# LoraSPI.net
KiCad netlist of a schematic drawn in Altium Designer
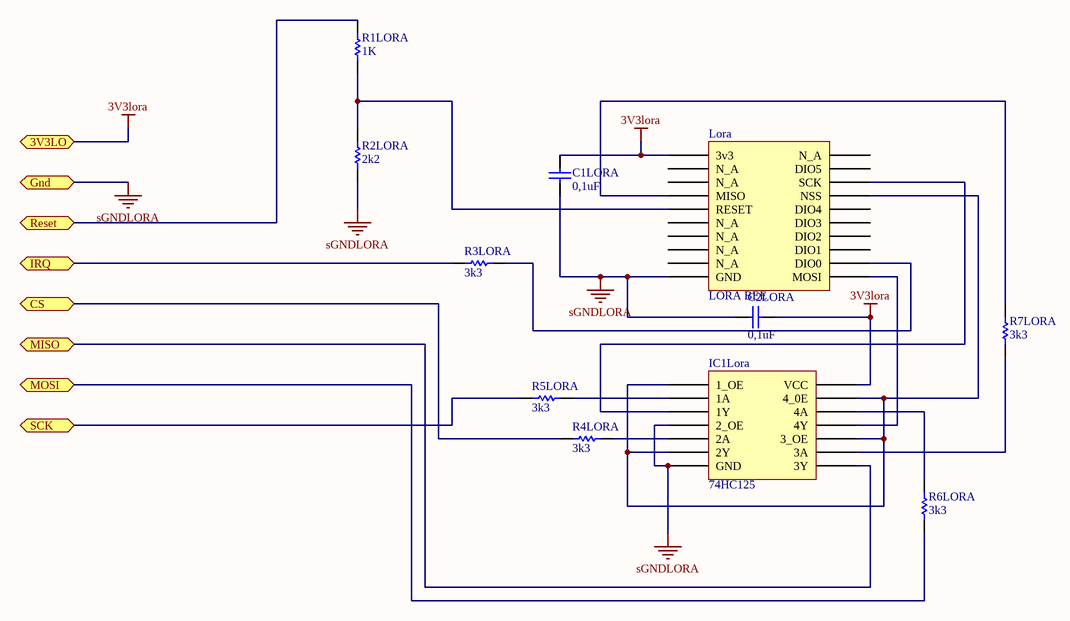
[diagram p0: LoraSPI.SchDoc]

(export (version "E")
  (design (tool "Eeschema 10.0.6"))
  (components
    (comp (ref "C1LORA")
      (value "0,1uF")
      (footprint "CAP100")
      (description "Capacitor")
      (libsource (lib "IDTILab") (part "CAP"))
    )
    (comp (ref "C2LORA")
      (value "0,1uF")
      (footprint "CAP100")
      (description "Capacitor")
      (libsource (lib "IDTILab") (part "CAP"))
    )
    (comp (ref "IC1Lora") (value "74HC125") (footprint "DIP14B") (libsource (lib "IDTILab") (part "74HC125")))
    (comp (ref "Lora") (value "LORA BEE") (footprint "LORABEE") (libsource (lib "IDTILab") (part "LORA BEE")))
    (comp (ref "R1LORA")
      (value "1K")
      (footprint "RES300")
      (description "Resistencia")
      (libsource (lib "IDTILab") (part "RES"))
    )
    (comp (ref "R2LORA")
      (value "2k2")
      (footprint "RES300")
      (description "Resistencia")
      (libsource (lib "IDTILab") (part "RES"))
    )
    (comp (ref "R3LORA")
      (value "3k3")
      (footprint "RES300")
      (description "Resistencia")
      (libsource (lib "IDTILab") (part "RES"))
    )
    (comp (ref "R4LORA")
      (value "3k3")
      (footprint "RES300")
      (description "Resistencia")
      (libsource (lib "IDTILab") (part "RES"))
    )
    (comp (ref "R5LORA")
      (value "3k3")
      (footprint "RES300")
      (description "Resistencia")
      (libsource (lib "IDTILab") (part "RES"))
    )
    (comp (ref "R6LORA")
      (value "3k3")
      (footprint "RES300")
      (description "Resistencia")
      (libsource (lib "IDTILab") (part "RES"))
    )
    (comp (ref "R7LORA")
      (value "3k3")
      (footprint "RES300")
      (description "Resistencia")
      (libsource (lib "IDTILab") (part "RES"))
    )
  )
  (nets
    (net (code "1") (name "/CS") (class "Default")
      (node (ref "R4LORA") (pin "2") (pinfunction "2_2") (pintype "passive"))
    )
    (net (code "2") (name "/IRQ") (class "Default")
      (node (ref "R3LORA") (pin "2") (pinfunction "2_2") (pintype "passive"))
    )
    (net (code "3") (name "/MISO") (class "Default")
      (node (ref "IC1Lora") (pin "8") (pinfunction "3Y_8") (pintype "passive"))
    )
    (net (code "4") (name "/MOSI") (class "Default")
      (node (ref "R6LORA") (pin "1") (pinfunction "1_1") (pintype "passive"))
    )
    (net (code "5") (name "/Reset") (class "Default")
      (node (ref "R1LORA") (pin "2") (pinfunction "2_2") (pintype "passive"))
    )
    (net (code "6") (name "/SCK") (class "Default")
      (node (ref "R5LORA") (pin "2") (pinfunction "2_2") (pintype "passive"))
    )
    (net (code "7") (name "3V3lora") (class "Default")
      (node (ref "C1LORA") (pin "2") (pinfunction "2_2") (pintype "passive"))
      (node (ref "C2LORA") (pin "2") (pinfunction "2_2") (pintype "passive"))
      (node (ref "IC1Lora") (pin "14") (pinfunction "VCC_14") (pintype "passive"))
      (node (ref "Lora") (pin "1") (pinfunction "3v3_1") (pintype "passive"))
    )
    (net (code "8") (name "Net-(IC1Lora-1A)") (class "Default")
      (node (ref "IC1Lora") (pin "2") (pinfunction "1A_2") (pintype "passive"))
      (node (ref "R5LORA") (pin "1") (pinfunction "1_1") (pintype "passive"))
    )
    (net (code "9") (name "Net-(IC1Lora-1Y)") (class "Default")
      (node (ref "IC1Lora") (pin "3") (pinfunction "1Y_3") (pintype "passive"))
      (node (ref "Lora") (pin "18") (pinfunction "SCK_18") (pintype "passive"))
    )
    (net (code "10") (name "Net-(IC1Lora-1_OE)") (class "Default")
      (node (ref "IC1Lora") (pin "1") (pinfunction "1_OE_1") (pintype "passive"))
      (node (ref "IC1Lora") (pin "10") (pinfunction "3_OE_10") (pintype "passive"))
      (node (ref "IC1Lora") (pin "13") (pinfunction "4_0E_13") (pintype "passive"))
      (node (ref "IC1Lora") (pin "6") (pinfunction "2Y_6") (pintype "passive"))
      (node (ref "Lora") (pin "17") (pinfunction "NSS_17") (pintype "passive"))
    )
    (net (code "11") (name "Net-(IC1Lora-2A)") (class "Default")
      (node (ref "IC1Lora") (pin "5") (pinfunction "2A_5") (pintype "passive"))
      (node (ref "R4LORA") (pin "1") (pinfunction "1_1") (pintype "passive"))
    )
    (net (code "12") (name "Net-(IC1Lora-3A)") (class "Default")
      (node (ref "IC1Lora") (pin "9") (pinfunction "3A_9") (pintype "passive"))
      (node (ref "R7LORA") (pin "1") (pinfunction "1_1") (pintype "passive"))
    )
    (net (code "13") (name "Net-(IC1Lora-4A)") (class "Default")
      (node (ref "IC1Lora") (pin "12") (pinfunction "4A_12") (pintype "passive"))
      (node (ref "R6LORA") (pin "2") (pinfunction "2_2") (pintype "passive"))
    )
    (net (code "14") (name "Net-(IC1Lora-4Y)") (class "Default")
      (node (ref "IC1Lora") (pin "11") (pinfunction "4Y_11") (pintype "passive"))
      (node (ref "Lora") (pin "11") (pinfunction "MOSI_11") (pintype "passive"))
    )
    (net (code "15") (name "Net-(Lora-DIO0)") (class "Default")
      (node (ref "Lora") (pin "12") (pinfunction "DIO0_12") (pintype "passive"))
      (node (ref "R3LORA") (pin "1") (pinfunction "1_1") (pintype "passive"))
    )
    (net (code "16") (name "Net-(Lora-MISO)") (class "Default")
      (node (ref "Lora") (pin "4") (pinfunction "MISO_4") (pintype "passive"))
      (node (ref "R7LORA") (pin "2") (pinfunction "2_2") (pintype "passive"))
    )
    (net (code "17") (name "Net-(Lora-RESET)") (class "Default")
      (node (ref "Lora") (pin "5") (pinfunction "RESET_5") (pintype "passive"))
      (node (ref "R1LORA") (pin "1") (pinfunction "1_1") (pintype "passive"))
      (node (ref "R2LORA") (pin "2") (pinfunction "2_2") (pintype "passive"))
    )
    (net (code "18") (name "sGNDLORA") (class "Default")
      (node (ref "C1LORA") (pin "1") (pinfunction "1_1") (pintype "passive"))
      (node (ref "C2LORA") (pin "1") (pinfunction "1_1") (pintype "passive"))
      (node (ref "IC1Lora") (pin "4") (pinfunction "2_OE_4") (pintype "passive"))
      (node (ref "IC1Lora") (pin "7") (pinfunction "GND_7") (pintype "passive"))
      (node (ref "Lora") (pin "10") (pinfunction "GND_10") (pintype "passive"))
      (node (ref "R2LORA") (pin "1") (pinfunction "1_1") (pintype "passive"))
    )
    (net (code "19") (name "unconnected-(Lora-DIO1-Pad13)") (class "Default")
      (node (ref "Lora") (pin "13") (pinfunction "DIO1_13") (pintype "passive"))
    )
    (net (code "20") (name "unconnected-(Lora-DIO2-Pad14)") (class "Default")
      (node (ref "Lora") (pin "14") (pinfunction "DIO2_14") (pintype "passive"))
    )
    (net (code "21") (name "unconnected-(Lora-DIO3-Pad15)") (class "Default")
      (node (ref "Lora") (pin "15") (pinfunction "DIO3_15") (pintype "passive"))
    )
    (net (code "22") (name "unconnected-(Lora-DIO4-Pad16)") (class "Default")
      (node (ref "Lora") (pin "16") (pinfunction "DIO4_16") (pintype "passive"))
    )
    (net (code "23") (name "unconnected-(Lora-DIO5-Pad19)") (class "Default")
      (node (ref "Lora") (pin "19") (pinfunction "DIO5_19") (pintype "passive"))
    )
    (net (code "24") (name "unconnected-(Lora-N_A-Pad2)") (class "Default")
      (node (ref "Lora") (pin "2") (pinfunction "N_A_2") (pintype "passive"))
    )
    (net (code "25") (name "unconnected-(Lora-N_A-Pad3)") (class "Default")
      (node (ref "Lora") (pin "3") (pinfunction "N_A_3") (pintype "passive"))
    )
    (net (code "26") (name "unconnected-(Lora-N_A-Pad6)") (class "Default")
      (node (ref "Lora") (pin "6") (pinfunction "N_A_6") (pintype "passive"))
    )
    (net (code "27") (name "unconnected-(Lora-N_A-Pad7)") (class "Default")
      (node (ref "Lora") (pin "7") (pinfunction "N_A_7") (pintype "passive"))
    )
    (net (code "28") (name "unconnected-(Lora-N_A-Pad8)") (class "Default")
      (node (ref "Lora") (pin "8") (pinfunction "N_A_8") (pintype "passive"))
    )
    (net (code "29") (name "unconnected-(Lora-N_A-Pad9)") (class "Default")
      (node (ref "Lora") (pin "9") (pinfunction "N_A_9") (pintype "passive"))
    )
    (net (code "30") (name "unconnected-(Lora-N_A-Pad20)") (class "Default")
      (node (ref "Lora") (pin "20") (pinfunction "N_A_20") (pintype "passive"))
    )
  )
)
